# ecg.net
KiCad netlist of a schematic drawn in EAGLE
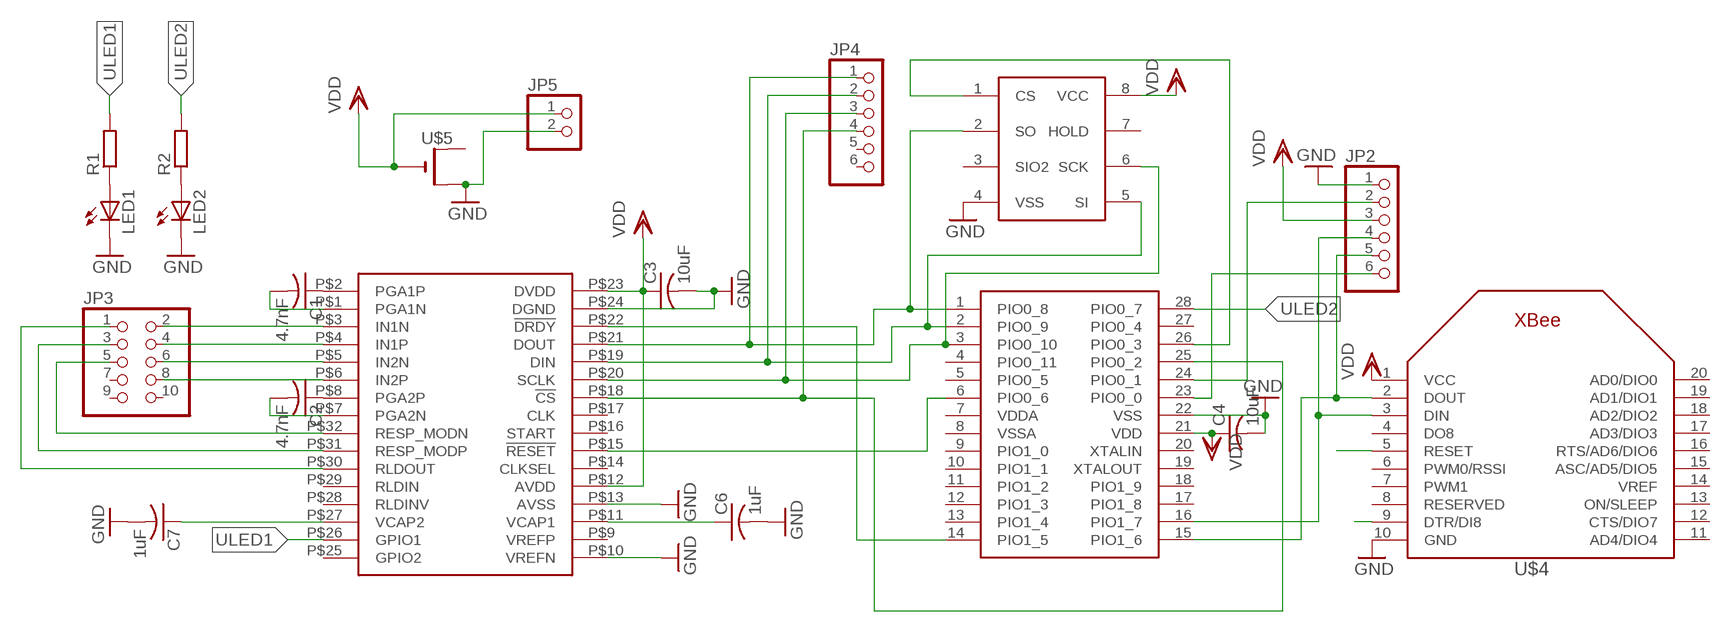
[diagram p0: schematic, sheet 1]

(export (version "E")
  (design (tool "Eeschema 10.0.6"))
  (components
    (comp (ref "C1")
      (value "4.7nF")
      (footprint "eagle-import:C0805")
      (libsource (lib "eagle-import") (part "C-USC0805"))
    )
    (comp (ref "C2")
      (value "4.7nF")
      (footprint "eagle-import:C0805")
      (libsource (lib "eagle-import") (part "C-USC0805"))
    )
    (comp (ref "C3")
      (value "10uF")
      (footprint "eagle-import:C0805")
      (libsource (lib "eagle-import") (part "C-USC0805"))
    )
    (comp (ref "C4")
      (value "10uF")
      (footprint "eagle-import:C0805")
      (libsource (lib "eagle-import") (part "C-USC0805"))
    )
    (comp (ref "C6")
      (value "1uF")
      (footprint "eagle-import:C0805")
      (libsource (lib "eagle-import") (part "C-USC0805"))
    )
    (comp (ref "C7")
      (value "1uF")
      (footprint "eagle-import:C0805")
      (libsource (lib "eagle-import") (part "C-USC0805"))
    )
    (comp (ref "JP2")
      (value "PINHD-1X6")
      (footprint "eagle-import:1X06")
      (libsource (lib "eagle-import") (part "PINHD-1X6"))
    )
    (comp (ref "JP3")
      (value "PINHD-2X5")
      (footprint "eagle-import:2X05")
      (libsource (lib "eagle-import") (part "PINHD-2X5"))
    )
    (comp (ref "JP4")
      (value "PINHD-1X6")
      (footprint "eagle-import:1X06")
      (libsource (lib "eagle-import") (part "PINHD-1X6"))
    )
    (comp (ref "JP5")
      (value "PINHD-1X2")
      (footprint "eagle-import:1X02")
      (libsource (lib "eagle-import") (part "PINHD-1X2"))
    )
    (comp (ref "LED1")
      (value "LED3MM")
      (footprint "eagle-import:LED3MM")
      (libsource (lib "eagle-import") (part "LED3MM"))
    )
    (comp (ref "LED2")
      (value "LED3MM")
      (footprint "eagle-import:LED3MM")
      (libsource (lib "eagle-import") (part "LED3MM"))
    )
    (comp (ref "R1")
      (value "R-EU_R0805")
      (footprint "eagle-import:R0805")
      (libsource (lib "eagle-import") (part "R-EU_R0805"))
    )
    (comp (ref "R2")
      (value "R-EU_R0805")
      (footprint "eagle-import:R0805")
      (libsource (lib "eagle-import") (part "R-EU_R0805"))
    )
    (comp (ref "U$1")
      (value "ADS1929R")
      (footprint "eagle-import:TQFP32")
      (libsource (lib "eagle-import") (part "ADS1929R"))
    )
    (comp (ref "U$2")
      (value "LPC1114FN28")
      (footprint "eagle-import:DIL28-6")
      (libsource (lib "eagle-import") (part "LPC1114FN28"))
    )
    (comp (ref "U$3")
      (value "23A1024")
      (footprint "eagle-import:DIL08")
      (libsource (lib "eagle-import") (part "23A1024"))
    )
    (comp (ref "U$4")
      (value "XBEE")
      (footprint "eagle-import:XBEE")
      (libsource (lib "eagle-import") (part "XBEE"))
    )
    (comp (ref "U$5")
      (value "CR2032SMT")
      (footprint "eagle-import:CR2032-SMD")
      (libsource (lib "eagle-import") (part "CR2032SMT"))
    )
  )
  (nets
    (net (code "1") (name "GND") (class "Default")
      (node (ref "C3") (pin "2") (pinfunction "2_2") (pintype "passive"))
      (node (ref "C4") (pin "2") (pinfunction "2_2") (pintype "passive"))
      (node (ref "C6") (pin "2") (pinfunction "2_2") (pintype "passive"))
      (node (ref "C7") (pin "2") (pinfunction "2_2") (pintype "passive"))
      (node (ref "JP2") (pin "1") (pinfunction "1_1") (pintype "passive"))
      (node (ref "JP5") (pin "2") (pinfunction "2_2") (pintype "passive"))
      (node (ref "LED1") (pin "K") (pinfunction "C_K") (pintype "passive"))
      (node (ref "LED2") (pin "K") (pinfunction "C_K") (pintype "passive"))
      (node (ref "U$1") (pin "P$10") (pinfunction "VREFN_P$10") (pintype "bidirectional"))
      (node (ref "U$1") (pin "P$13") (pinfunction "AVSS_P$13") (pintype "bidirectional"))
      (node (ref "U$1") (pin "P$24") (pinfunction "DGND_P$24") (pintype "bidirectional"))
      (node (ref "U$2") (pin "22") (pinfunction "VSS_22") (pintype "bidirectional"))
      (node (ref "U$3") (pin "4") (pinfunction "VSS_4") (pintype "bidirectional"))
      (node (ref "U$4") (pin "10") (pinfunction "GND_10") (pintype "power_in"))
      (node (ref "U$5") (pin "+$2") (pinfunction "+1_+$2") (pintype "passive"))
    )
    (net (code "2") (name "Net-(LED1-PadA)") (class "Default")
      (node (ref "LED1") (pin "A") (pinfunction "A_A") (pintype "passive"))
      (node (ref "R1") (pin "1") (pinfunction "1_1") (pintype "passive"))
    )
    (net (code "3") (name "Net-(LED2-PadA)") (class "Default")
      (node (ref "LED2") (pin "A") (pinfunction "A_A") (pintype "passive"))
      (node (ref "R2") (pin "1") (pinfunction "1_1") (pintype "passive"))
    )
    (net (code "4") (name "Net-(U$1-DIN)") (class "Default")
      (node (ref "JP4") (pin "2") (pinfunction "2_2") (pintype "passive"))
      (node (ref "U$1") (pin "P$19") (pinfunction "DIN_P$19") (pintype "bidirectional"))
      (node (ref "U$2") (pin "2") (pinfunction "PIO0_9_2") (pintype "bidirectional"))
      (node (ref "U$3") (pin "5") (pinfunction "SI_5") (pintype "bidirectional"))
    )
    (net (code "5") (name "Net-(U$1-DOUT)") (class "Default")
      (node (ref "JP4") (pin "1") (pinfunction "1_1") (pintype "passive"))
      (node (ref "U$1") (pin "P$21") (pinfunction "DOUT_P$21") (pintype "bidirectional"))
      (node (ref "U$2") (pin "1") (pinfunction "PIO0_8_1") (pintype "bidirectional"))
      (node (ref "U$3") (pin "2") (pinfunction "SO_2") (pintype "bidirectional"))
    )
    (net (code "6") (name "Net-(U$1-IN1N)") (class "Default")
      (node (ref "JP3") (pin "2") (pinfunction "2_2") (pintype "passive"))
      (node (ref "U$1") (pin "P$3") (pinfunction "IN1N_P$3") (pintype "bidirectional"))
    )
    (net (code "7") (name "Net-(U$1-IN1P)") (class "Default")
      (node (ref "JP3") (pin "4") (pinfunction "4_4") (pintype "passive"))
      (node (ref "U$1") (pin "P$4") (pinfunction "IN1P_P$4") (pintype "bidirectional"))
    )
    (net (code "8") (name "Net-(U$1-IN2N)") (class "Default")
      (node (ref "JP3") (pin "6") (pinfunction "6_6") (pintype "passive"))
      (node (ref "U$1") (pin "P$5") (pinfunction "IN2N_P$5") (pintype "bidirectional"))
    )
    (net (code "9") (name "Net-(U$1-IN2P)") (class "Default")
      (node (ref "JP3") (pin "8") (pinfunction "8_8") (pintype "passive"))
      (node (ref "U$1") (pin "P$6") (pinfunction "IN2P_P$6") (pintype "bidirectional"))
    )
    (net (code "10") (name "Net-(U$1-PGA1N)") (class "Default")
      (node (ref "C1") (pin "2") (pinfunction "2_2") (pintype "passive"))
      (node (ref "U$1") (pin "P$1") (pinfunction "PGA1N_P$1") (pintype "bidirectional"))
    )
    (net (code "11") (name "Net-(U$1-PGA1P)") (class "Default")
      (node (ref "C1") (pin "1") (pinfunction "1_1") (pintype "passive"))
      (node (ref "U$1") (pin "P$2") (pinfunction "PGA1P_P$2") (pintype "bidirectional"))
    )
    (net (code "12") (name "Net-(U$1-PGA2N)") (class "Default")
      (node (ref "C2") (pin "2") (pinfunction "2_2") (pintype "passive"))
      (node (ref "U$1") (pin "P$7") (pinfunction "PGA2N_P$7") (pintype "bidirectional"))
    )
    (net (code "13") (name "Net-(U$1-PGA2P)") (class "Default")
      (node (ref "C2") (pin "1") (pinfunction "1_1") (pintype "passive"))
      (node (ref "U$1") (pin "P$8") (pinfunction "PGA2P_P$8") (pintype "bidirectional"))
    )
    (net (code "14") (name "Net-(U$1-RESP_MODN)") (class "Default")
      (node (ref "JP3") (pin "5") (pinfunction "5_5") (pintype "passive"))
      (node (ref "U$1") (pin "P$32") (pinfunction "RESP_MODN_P$32") (pintype "bidirectional"))
    )
    (net (code "15") (name "Net-(U$1-RESP_MODP)") (class "Default")
      (node (ref "JP3") (pin "3") (pinfunction "3_3") (pintype "passive"))
      (node (ref "U$1") (pin "P$31") (pinfunction "RESP_MODP_P$31") (pintype "bidirectional"))
    )
    (net (code "16") (name "Net-(U$1-RLDOUT)") (class "Default")
      (node (ref "JP3") (pin "1") (pinfunction "1_1") (pintype "passive"))
      (node (ref "U$1") (pin "P$30") (pinfunction "RLDOUT_P$30") (pintype "bidirectional"))
    )
    (net (code "17") (name "Net-(U$1-SCLK)") (class "Default")
      (node (ref "JP4") (pin "3") (pinfunction "3_3") (pintype "passive"))
      (node (ref "U$1") (pin "P$20") (pinfunction "SCLK_P$20") (pintype "bidirectional"))
      (node (ref "U$2") (pin "3") (pinfunction "PIO0_10_3") (pintype "bidirectional"))
      (node (ref "U$3") (pin "6") (pinfunction "SCK_6") (pintype "bidirectional"))
    )
    (net (code "18") (name "Net-(U$1-VCAP1)") (class "Default")
      (node (ref "C6") (pin "1") (pinfunction "1_1") (pintype "passive"))
      (node (ref "U$1") (pin "P$11") (pinfunction "VCAP1_P$11") (pintype "bidirectional"))
    )
    (net (code "19") (name "Net-(U$1-VCAP2)") (class "Default")
      (node (ref "C7") (pin "1") (pinfunction "1_1") (pintype "passive"))
      (node (ref "U$1") (pin "P$27") (pinfunction "VCAP2_P$27") (pintype "bidirectional"))
    )
    (net (code "20") (name "Net-(U$1-~{CS})") (class "Default")
      (node (ref "JP4") (pin "4") (pinfunction "4_4") (pintype "passive"))
      (node (ref "U$1") (pin "P$18") (pinfunction "~{CS}_P$18") (pintype "bidirectional"))
      (node (ref "U$2") (pin "25") (pinfunction "PIO0_2_25") (pintype "bidirectional"))
    )
    (net (code "21") (name "Net-(U$1-~{DRDY})") (class "Default")
      (node (ref "U$1") (pin "P$22") (pinfunction "~{DRDY}_P$22") (pintype "bidirectional"))
      (node (ref "U$2") (pin "14") (pinfunction "PIO1_5_14") (pintype "bidirectional"))
    )
    (net (code "22") (name "Net-(U$1-~{RESET})") (class "Default")
      (node (ref "U$1") (pin "P$15") (pinfunction "~{RESET}_P$15") (pintype "bidirectional"))
      (node (ref "U$2") (pin "6") (pinfunction "PIO0_6_6") (pintype "bidirectional"))
    )
    (net (code "23") (name "Net-(U$2-PIO0_0)") (class "Default")
      (node (ref "JP2") (pin "6") (pinfunction "6_6") (pintype "passive"))
      (node (ref "U$2") (pin "23") (pinfunction "PIO0_0_23") (pintype "bidirectional"))
    )
    (net (code "24") (name "Net-(U$2-PIO0_1)") (class "Default")
      (node (ref "JP2") (pin "2") (pinfunction "2_2") (pintype "passive"))
      (node (ref "U$2") (pin "24") (pinfunction "PIO0_1_24") (pintype "bidirectional"))
    )
    (net (code "25") (name "Net-(U$2-PIO0_3)") (class "Default")
      (node (ref "U$2") (pin "26") (pinfunction "PIO0_3_26") (pintype "bidirectional"))
      (node (ref "U$3") (pin "1") (pinfunction "CS_1") (pintype "bidirectional"))
    )
    (net (code "26") (name "Net-(U$2-PIO1_6)") (class "Default")
      (node (ref "JP2") (pin "5") (pinfunction "5_5") (pintype "passive"))
      (node (ref "U$2") (pin "15") (pinfunction "PIO1_6_15") (pintype "bidirectional"))
      (node (ref "U$4") (pin "2") (pinfunction "DOUT_2") (pintype "output"))
    )
    (net (code "27") (name "Net-(U$2-PIO1_7)") (class "Default")
      (node (ref "JP2") (pin "4") (pinfunction "4_4") (pintype "passive"))
      (node (ref "U$2") (pin "16") (pinfunction "PIO1_7_16") (pintype "bidirectional"))
      (node (ref "U$4") (pin "3") (pinfunction "DIN_3") (pintype "input"))
    )
    (net (code "28") (name "ULED1") (class "Default")
      (node (ref "R1") (pin "2") (pinfunction "2_2") (pintype "passive"))
      (node (ref "U$1") (pin "P$26") (pinfunction "GPIO1_P$26") (pintype "bidirectional"))
    )
    (net (code "29") (name "ULED2") (class "Default")
      (node (ref "R2") (pin "2") (pinfunction "2_2") (pintype "passive"))
      (node (ref "U$2") (pin "28") (pinfunction "PIO0_7_28") (pintype "bidirectional"))
    )
    (net (code "30") (name "VDD") (class "Default")
      (node (ref "C3") (pin "1") (pinfunction "1_1") (pintype "passive"))
      (node (ref "C4") (pin "1") (pinfunction "1_1") (pintype "passive"))
      (node (ref "JP2") (pin "3") (pinfunction "3_3") (pintype "passive"))
      (node (ref "JP5") (pin "1") (pinfunction "1_1") (pintype "passive"))
      (node (ref "U$1") (pin "P$12") (pinfunction "AVDD_P$12") (pintype "bidirectional"))
      (node (ref "U$1") (pin "P$23") (pinfunction "DVDD_P$23") (pintype "bidirectional"))
      (node (ref "U$2") (pin "21") (pinfunction "VDD_21") (pintype "bidirectional"))
      (node (ref "U$3") (pin "8") (pinfunction "VCC_8") (pintype "bidirectional"))
      (node (ref "U$4") (pin "1") (pinfunction "VCC_1") (pintype "power_in"))
      (node (ref "U$5") (pin "-") (pinfunction "-_-") (pintype "passive"))
    )
    (net (code "31") (name "unconnected-(JP3-Pad7)") (class "Default")
      (node (ref "JP3") (pin "7") (pinfunction "7_7") (pintype "passive"))
    )
    (net (code "32") (name "unconnected-(JP3-Pad9)") (class "Default")
      (node (ref "JP3") (pin "9") (pinfunction "9_9") (pintype "passive"))
    )
    (net (code "33") (name "unconnected-(JP3-Pad10)") (class "Default")
      (node (ref "JP3") (pin "10") (pinfunction "10_10") (pintype "passive"))
    )
    (net (code "34") (name "unconnected-(JP4-Pad5)") (class "Default")
      (node (ref "JP4") (pin "5") (pinfunction "5_5") (pintype "passive"))
    )
    (net (code "35") (name "unconnected-(JP4-Pad6)") (class "Default")
      (node (ref "JP4") (pin "6") (pinfunction "6_6") (pintype "passive"))
    )
    (net (code "36") (name "unconnected-(U$1-CLK-PadP$17)") (class "Default")
      (node (ref "U$1") (pin "P$17") (pinfunction "CLK_P$17") (pintype "bidirectional"))
    )
    (net (code "37") (name "unconnected-(U$1-CLKSEL-PadP$14)") (class "Default")
      (node (ref "U$1") (pin "P$14") (pinfunction "CLKSEL_P$14") (pintype "bidirectional"))
    )
    (net (code "38") (name "unconnected-(U$1-GPIO2-PadP$25)") (class "Default")
      (node (ref "U$1") (pin "P$25") (pinfunction "GPIO2_P$25") (pintype "bidirectional"))
    )
    (net (code "39") (name "unconnected-(U$1-RLDIN-PadP$29)") (class "Default")
      (node (ref "U$1") (pin "P$29") (pinfunction "RLDIN_P$29") (pintype "bidirectional"))
    )
    (net (code "40") (name "unconnected-(U$1-RLDINV-PadP$28)") (class "Default")
      (node (ref "U$1") (pin "P$28") (pinfunction "RLDINV_P$28") (pintype "bidirectional"))
    )
    (net (code "41") (name "unconnected-(U$1-START-PadP$16)") (class "Default")
      (node (ref "U$1") (pin "P$16") (pinfunction "START_P$16") (pintype "bidirectional"))
    )
    (net (code "42") (name "unconnected-(U$1-VREFP-PadP$9)") (class "Default")
      (node (ref "U$1") (pin "P$9") (pinfunction "VREFP_P$9") (pintype "bidirectional"))
    )
    (net (code "43") (name "unconnected-(U$2-PIO0_4-Pad27)") (class "Default")
      (node (ref "U$2") (pin "27") (pinfunction "PIO0_4_27") (pintype "bidirectional"))
    )
    (net (code "44") (name "unconnected-(U$2-PIO0_5-Pad5)") (class "Default")
      (node (ref "U$2") (pin "5") (pinfunction "PIO0_5_5") (pintype "bidirectional"))
    )
    (net (code "45") (name "unconnected-(U$2-PIO0_11-Pad4)") (class "Default")
      (node (ref "U$2") (pin "4") (pinfunction "PIO0_11_4") (pintype "bidirectional"))
    )
    (net (code "46") (name "unconnected-(U$2-PIO1_0-Pad9)") (class "Default")
      (node (ref "U$2") (pin "9") (pinfunction "PIO1_0_9") (pintype "bidirectional"))
    )
    (net (code "47") (name "unconnected-(U$2-PIO1_1-Pad10)") (class "Default")
      (node (ref "U$2") (pin "10") (pinfunction "PIO1_1_10") (pintype "bidirectional"))
    )
    (net (code "48") (name "unconnected-(U$2-PIO1_2-Pad11)") (class "Default")
      (node (ref "U$2") (pin "11") (pinfunction "PIO1_2_11") (pintype "bidirectional"))
    )
    (net (code "49") (name "unconnected-(U$2-PIO1_3-Pad12)") (class "Default")
      (node (ref "U$2") (pin "12") (pinfunction "PIO1_3_12") (pintype "bidirectional"))
    )
    (net (code "50") (name "unconnected-(U$2-PIO1_4-Pad13)") (class "Default")
      (node (ref "U$2") (pin "13") (pinfunction "PIO1_4_13") (pintype "bidirectional"))
    )
    (net (code "51") (name "unconnected-(U$2-PIO1_8-Pad17)") (class "Default")
      (node (ref "U$2") (pin "17") (pinfunction "PIO1_8_17") (pintype "bidirectional"))
    )
    (net (code "52") (name "unconnected-(U$2-PIO1_9-Pad18)") (class "Default")
      (node (ref "U$2") (pin "18") (pinfunction "PIO1_9_18") (pintype "bidirectional"))
    )
    (net (code "53") (name "unconnected-(U$2-VDDA-Pad7)") (class "Default")
      (node (ref "U$2") (pin "7") (pinfunction "VDDA_7") (pintype "bidirectional"))
    )
    (net (code "54") (name "unconnected-(U$2-VSSA-Pad8)") (class "Default")
      (node (ref "U$2") (pin "8") (pinfunction "VSSA_8") (pintype "bidirectional"))
    )
    (net (code "55") (name "unconnected-(U$2-XTALIN-Pad20)") (class "Default")
      (node (ref "U$2") (pin "20") (pinfunction "XTALIN_20") (pintype "bidirectional"))
    )
    (net (code "56") (name "unconnected-(U$2-XTALOUT-Pad19)") (class "Default")
      (node (ref "U$2") (pin "19") (pinfunction "XTALOUT_19") (pintype "bidirectional"))
    )
    (net (code "57") (name "unconnected-(U$3-HOLD-Pad7)") (class "Default")
      (node (ref "U$3") (pin "7") (pinfunction "HOLD_7") (pintype "bidirectional"))
    )
    (net (code "58") (name "unconnected-(U$3-SIO2-Pad3)") (class "Default")
      (node (ref "U$3") (pin "3") (pinfunction "SIO2_3") (pintype "bidirectional"))
    )
    (net (code "59") (name "unconnected-(U$4-AD0{slash}DIO0-Pad20)") (class "Default")
      (node (ref "U$4") (pin "20") (pinfunction "AD0/DIO0_20") (pintype "bidirectional"))
    )
    (net (code "60") (name "unconnected-(U$4-AD1{slash}DIO1-Pad19)") (class "Default")
      (node (ref "U$4") (pin "19") (pinfunction "AD1/DIO1_19") (pintype "bidirectional"))
    )
    (net (code "61") (name "unconnected-(U$4-AD2{slash}DIO2-Pad18)") (class "Default")
      (node (ref "U$4") (pin "18") (pinfunction "AD2/DIO2_18") (pintype "bidirectional"))
    )
    (net (code "62") (name "unconnected-(U$4-AD3{slash}DIO3-Pad17)") (class "Default")
      (node (ref "U$4") (pin "17") (pinfunction "AD3/DIO3_17") (pintype "bidirectional"))
    )
    (net (code "63") (name "unconnected-(U$4-AD4{slash}DIO4-Pad11)") (class "Default")
      (node (ref "U$4") (pin "11") (pinfunction "AD4/DIO4_11") (pintype "bidirectional"))
    )
    (net (code "64") (name "unconnected-(U$4-ASC{slash}AD5{slash}DIO5-Pad15)") (class "Default")
      (node (ref "U$4") (pin "15") (pinfunction "ASC/AD5/DIO5_15") (pintype "bidirectional"))
    )
    (net (code "65") (name "unconnected-(U$4-CTS{slash}DIO7-Pad12)") (class "Default")
      (node (ref "U$4") (pin "12") (pinfunction "CTS/DIO7_12") (pintype "bidirectional"))
    )
    (net (code "66") (name "unconnected-(U$4-DO8-Pad4)") (class "Default")
      (node (ref "U$4") (pin "4") (pinfunction "DO8_4") (pintype "output"))
    )
    (net (code "67") (name "unconnected-(U$4-DTR{slash}DI8-Pad9)") (class "Default")
      (node (ref "U$4") (pin "9") (pinfunction "DTR/DI8_9") (pintype "input"))
    )
    (net (code "68") (name "unconnected-(U$4-ON{slash}SLEEP-Pad13)") (class "Default")
      (node (ref "U$4") (pin "13") (pinfunction "ON/SLEEP_13") (pintype "output"))
    )
    (net (code "69") (name "unconnected-(U$4-PWM0{slash}RSSI-Pad6)") (class "Default")
      (node (ref "U$4") (pin "6") (pinfunction "PWM0/RSSI_6") (pintype "output"))
    )
    (net (code "70") (name "unconnected-(U$4-PWM1-Pad7)") (class "Default")
      (node (ref "U$4") (pin "7") (pinfunction "PWM1_7") (pintype "output"))
    )
    (net (code "71") (name "unconnected-(U$4-RESERVED-Pad8)") (class "Default")
      (node (ref "U$4") (pin "8") (pinfunction "RESERVED_8") (pintype "no_connect"))
    )
    (net (code "72") (name "unconnected-(U$4-RESET-Pad5)") (class "Default")
      (node (ref "U$4") (pin "5") (pinfunction "RESET_5") (pintype "input"))
    )
    (net (code "73") (name "unconnected-(U$4-RTS{slash}AD6{slash}DIO6-Pad16)") (class "Default")
      (node (ref "U$4") (pin "16") (pinfunction "RTS/AD6/DIO6_16") (pintype "bidirectional"))
    )
    (net (code "74") (name "unconnected-(U$4-VREF-Pad14)") (class "Default")
      (node (ref "U$4") (pin "14") (pinfunction "VREF_14") (pintype "input"))
    )
    (net (code "75") (name "unconnected-(U$5-+-Pad+$1)") (class "Default")
      (node (ref "U$5") (pin "+$1") (pinfunction "+_+$1") (pintype "passive"))
    )
  )
)
